# lab_1_kapustin_usb_spi.net
KiCad netlist of a schematic drawn in Altium Designer
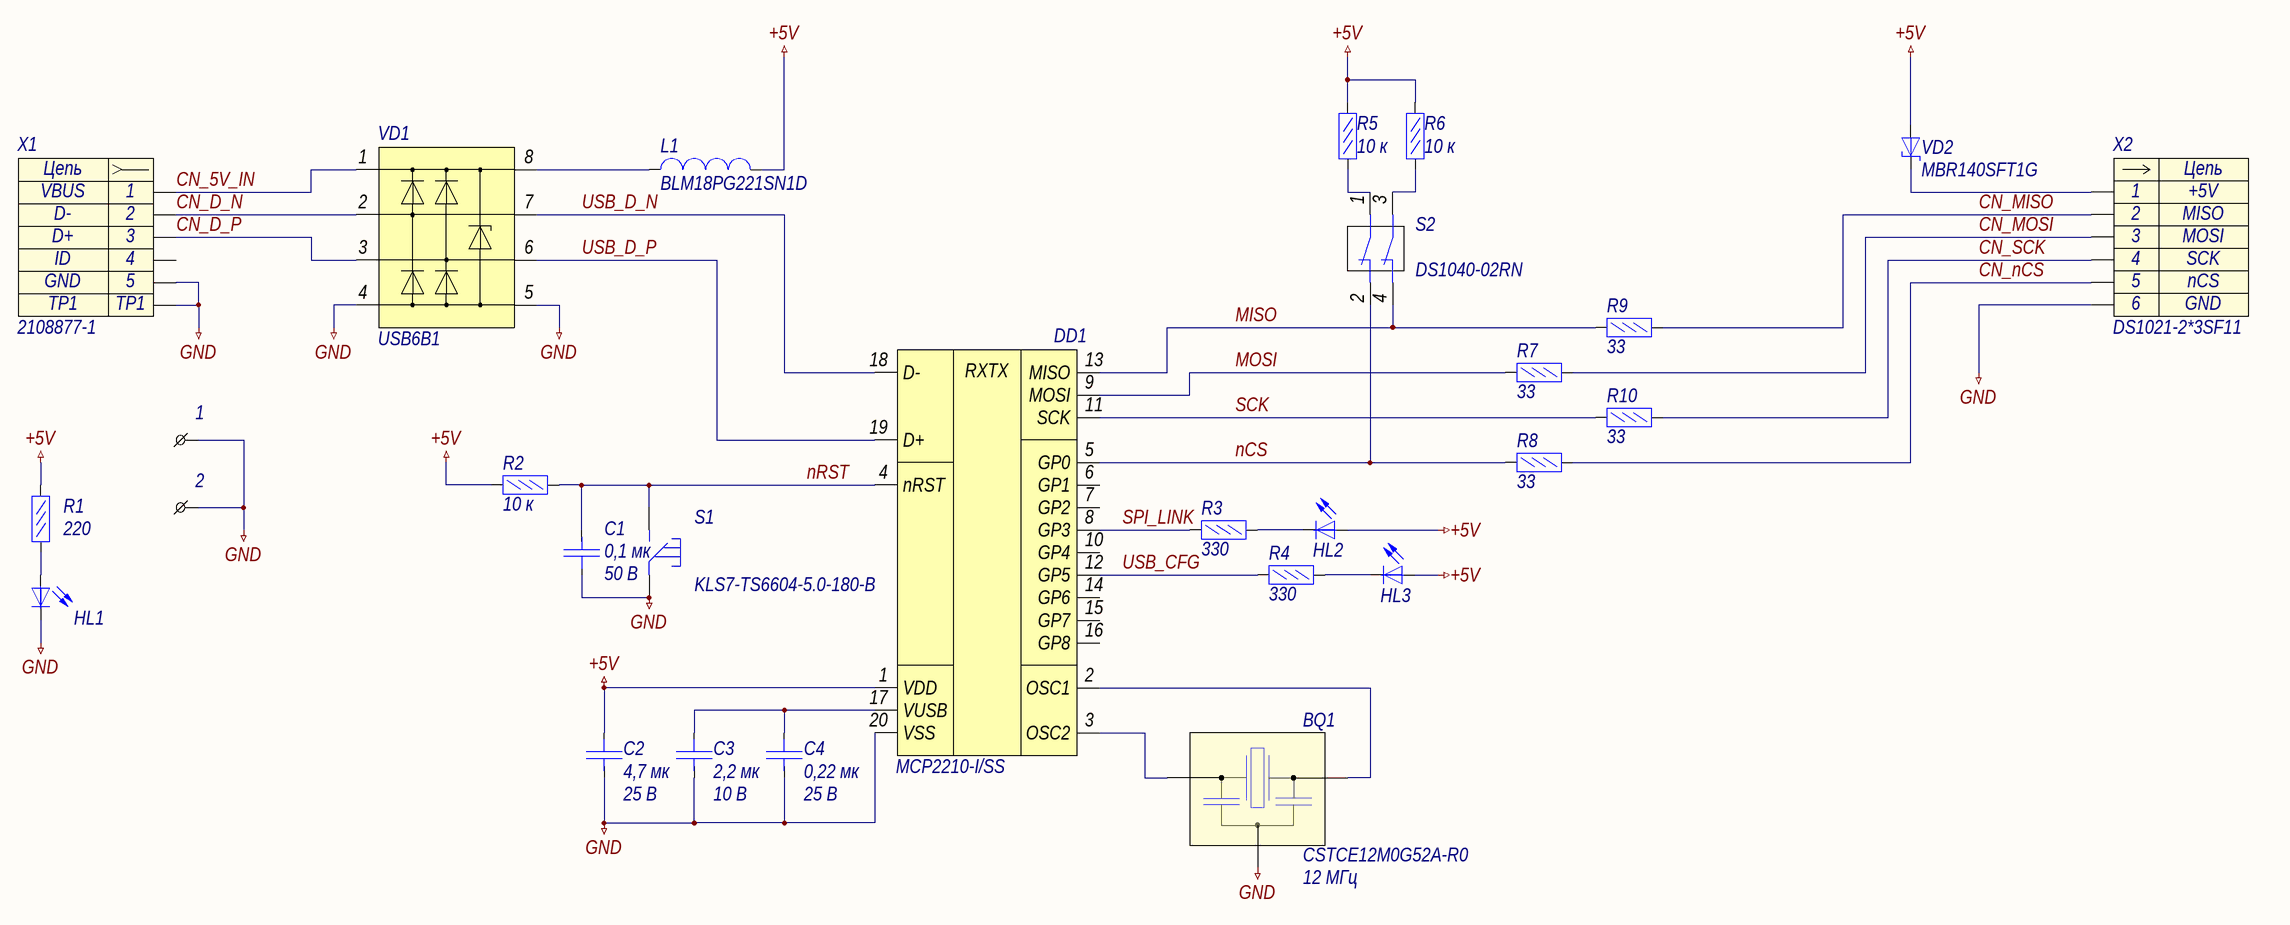
[diagram p0: lab_1_kapustin_usb_spi.SchDoc]

(export (version "E")
  (design (tool "Eeschema 10.0.6"))
  (components
    (comp (ref "1")
      (value "MOUNTING_HOLE")
      (footprint "HOLE_1,6X3,3")
      (libsource (lib "kravt_lib") (part "MOUNTING_HOLE"))
    )
    (comp (ref "2")
      (value "MOUNTING_HOLE")
      (footprint "HOLE_1,6X3,3")
      (libsource (lib "kravt_lib") (part "MOUNTING_HOLE"))
    )
    (comp (ref "BQ1")
      (value "CSTCE12M0G52A-R0")
      (footprint "CSTCE-3_320x130x40")
      (fields (field (name "ЧАСТОТА") "12 МГц"))
      (libsource (lib "kravt_lib") (part "cstce12m0g52a-r0"))
    )
    (comp (ref "C1")
      (value "0,1 мк")
      (footprint "C0603")
      (description "Конденсатор")
      (fields (field (name "НАПРЯЖЕНИЕ") "50 В"))
      (libsource (lib "kravt_lib") (part "c"))
    )
    (comp (ref "C2")
      (value "4,7 мк")
      (footprint "C0603")
      (description "Конденсатор")
      (fields (field (name "НАПРЯЖЕНИЕ") "25 В"))
      (libsource (lib "kravt_lib") (part "c"))
    )
    (comp (ref "C3")
      (value "2,2 мк")
      (footprint "C0603")
      (description "Конденсатор")
      (fields (field (name "НАПРЯЖЕНИЕ") "10 В"))
      (libsource (lib "kravt_lib") (part "c"))
    )
    (comp (ref "C4")
      (value "0,22 мк")
      (footprint "C0603")
      (description "Конденсатор")
      (fields (field (name "НАПРЯЖЕНИЕ") "25 В"))
      (libsource (lib "kravt_lib") (part "c"))
    )
    (comp (ref "DD1")
      (value "MCP2210-I/SS")
      (footprint "ssop-20_780x720x200:SSOP-20_780x720x200")
      (libsource (lib "MCP2210-ISS") (part "MCP2210ISS"))
    )
    (comp (ref "HL1")
      (value "KP-1608SGC")
      (footprint "D0603")
      (libsource (lib "kravt_lib") (part "DIODE_LED"))
    )
    (comp (ref "HL2")
      (value "KP-1608YC")
      (footprint "D0603")
      (libsource (lib "kravt_lib") (part "DIODE_LED"))
    )
    (comp (ref "HL3")
      (value "KP-1608YC")
      (footprint "D0603")
      (libsource (lib "kravt_lib") (part "DIODE_LED"))
    )
    (comp (ref "L1")
      (value "BLM18PG221SN1D")
      (footprint "L0603")
      (libsource (lib "kravt_lib") (part "L_BEAD"))
    )
    (comp (ref "R1")
      (value "220")
      (footprint "R0603")
      (description "Резистор 0,063Вт")
      (libsource (lib "kravt_lib") (part "R-0.063W"))
    )
    (comp (ref "R2")
      (value "10 к")
      (footprint "R0603")
      (description "Резистор 0,063Вт")
      (libsource (lib "") (part "R-0.063W_1"))
    )
    (comp (ref "R3")
      (value "330")
      (footprint "R0603")
      (description "Резистор 0,063Вт")
      (libsource (lib "") (part "R-0.063W_1"))
    )
    (comp (ref "R4")
      (value "330")
      (footprint "R0603")
      (description "Резистор 0,063Вт")
      (libsource (lib "") (part "R-0.063W_1"))
    )
    (comp (ref "R5")
      (value "10 к")
      (footprint "R0603")
      (description "Резистор 0,063Вт")
      (libsource (lib "kravt_lib") (part "R-0.063W"))
    )
    (comp (ref "R6")
      (value "10 к")
      (footprint "R0603")
      (description "Резистор 0,063Вт")
      (libsource (lib "kravt_lib") (part "R-0.063W"))
    )
    (comp (ref "R7")
      (value "33")
      (footprint "R0603")
      (description "Резистор 0,063Вт")
      (libsource (lib "") (part "R-0.063W_1"))
    )
    (comp (ref "R8")
      (value "33")
      (footprint "R0603")
      (description "Резистор 0,063Вт")
      (libsource (lib "") (part "R-0.063W_1"))
    )
    (comp (ref "R9")
      (value "33")
      (footprint "R0603")
      (description "Резистор 0,063Вт")
      (libsource (lib "") (part "R-0.063W_1"))
    )
    (comp (ref "R10")
      (value "33")
      (footprint "R0603")
      (description "Резистор 0,063Вт")
      (libsource (lib "") (part "R-0.063W_1"))
    )
    (comp (ref "S1")
      (value "KLS7-TS6604-5.0-180-B")
      (footprint "KLS7-TS6604_500")
      (libsource (lib "kravt_lib") (part "BUTTON"))
    )
    (comp (ref "S2")
      (value "DS1040-02RN")
      (footprint "DS1040-02RN")
      (libsource (lib "kravt_lib") (part "SWITCH_2C"))
    )
    (comp (ref "VD1") (value "USB6B1") (footprint "SO-8") (libsource (lib "kravt_lib") (part "USB6B1")))
    (comp (ref "VD2")
      (value "MBR140SFT1G")
      (footprint "SOD-123FL_290X180X98")
      (libsource (lib "kravt_lib") (part "DIODE_SHOTTKY"))
    )
    (comp (ref "X1")
      (value "2108877-1")
      (footprint "2108877-1")
      (libsource (lib "2108877-1_micro_usb-b") (part "2108877-1_micro_usb-b"))
    )
    (comp (ref "X2")
      (value "DS1021-2*3SF11")
      (footprint "PLS-2,54-2X3-THT-V")
      (libsource (lib "kravt_lib") (part "HEADER-6_PLG"))
    )
  )
  (nets
    (net (code "1") (name "+5V") (class "Default")
      (node (ref "C2") (pin "1") (pinfunction "1_1") (pintype "passive"))
      (node (ref "DD1") (pin "1") (pinfunction "VDD_1") (pintype "passive"))
      (node (ref "HL2") (pin "1") (pinfunction "A_1") (pintype "passive"))
      (node (ref "HL3") (pin "1") (pinfunction "A_1") (pintype "passive"))
      (node (ref "L1") (pin "2") (pinfunction "2_2") (pintype "passive"))
      (node (ref "R1") (pin "2") (pinfunction "2_2") (pintype "passive"))
      (node (ref "R2") (pin "1") (pinfunction "1_1") (pintype "passive"))
      (node (ref "R5") (pin "2") (pinfunction "2_2") (pintype "passive"))
      (node (ref "R6") (pin "2") (pinfunction "2_2") (pintype "passive"))
      (node (ref "VD2") (pin "1") (pinfunction "A_1") (pintype "passive"))
    )
    (net (code "2") (name "/CN_5V_IN") (class "Default")
      (node (ref "VD1") (pin "1") (pintype "passive"))
      (node (ref "X1") (pin "1") (pinfunction "1_1") (pintype "passive"))
    )
    (net (code "3") (name "/CN_D_N") (class "Default")
      (node (ref "VD1") (pin "2") (pintype "passive"))
      (node (ref "X1") (pin "2") (pinfunction "2_2") (pintype "passive"))
    )
    (net (code "4") (name "/CN_D_P") (class "Default")
      (node (ref "VD1") (pin "3") (pintype "passive"))
      (node (ref "X1") (pin "3") (pinfunction "3_3") (pintype "passive"))
    )
    (net (code "5") (name "/CN_MISO") (class "Default")
      (node (ref "R9") (pin "2") (pinfunction "2_2") (pintype "passive"))
      (node (ref "X2") (pin "2") (pinfunction "2_2") (pintype "passive"))
    )
    (net (code "6") (name "/CN_MOSI") (class "Default")
      (node (ref "R7") (pin "2") (pinfunction "2_2") (pintype "passive"))
      (node (ref "X2") (pin "3") (pinfunction "3_3") (pintype "passive"))
    )
    (net (code "7") (name "/CN_SCK") (class "Default")
      (node (ref "R10") (pin "2") (pinfunction "2_2") (pintype "passive"))
      (node (ref "X2") (pin "4") (pinfunction "4_4") (pintype "passive"))
    )
    (net (code "8") (name "/CN_nCS") (class "Default")
      (node (ref "R8") (pin "2") (pinfunction "2_2") (pintype "passive"))
      (node (ref "X2") (pin "5") (pinfunction "5_5") (pintype "passive"))
    )
    (net (code "9") (name "/MISO") (class "Default")
      (node (ref "DD1") (pin "13") (pinfunction "MISO_13") (pintype "passive"))
      (node (ref "R9") (pin "1") (pinfunction "1_1") (pintype "passive"))
      (node (ref "S2") (pin "4") (pinfunction "4_4") (pintype "passive"))
    )
    (net (code "10") (name "/MOSI") (class "Default")
      (node (ref "DD1") (pin "9") (pinfunction "MOSI_9") (pintype "passive"))
      (node (ref "R7") (pin "1") (pinfunction "1_1") (pintype "passive"))
    )
    (net (code "11") (name "/SCK") (class "Default")
      (node (ref "DD1") (pin "11") (pinfunction "SCK_11") (pintype "passive"))
      (node (ref "R10") (pin "1") (pinfunction "1_1") (pintype "passive"))
    )
    (net (code "12") (name "/SPI_LINK") (class "Default")
      (node (ref "DD1") (pin "8") (pinfunction "GP3_8") (pintype "passive"))
      (node (ref "R3") (pin "1") (pinfunction "1_1") (pintype "passive"))
    )
    (net (code "13") (name "/USB_CFG") (class "Default")
      (node (ref "DD1") (pin "12") (pinfunction "GP5_12") (pintype "passive"))
      (node (ref "R4") (pin "1") (pinfunction "1_1") (pintype "passive"))
    )
    (net (code "14") (name "/USB_D_N") (class "Default")
      (node (ref "DD1") (pin "18") (pinfunction "D-_18") (pintype "passive"))
      (node (ref "VD1") (pin "7") (pintype "passive"))
    )
    (net (code "15") (name "/USB_D_P") (class "Default")
      (node (ref "DD1") (pin "19") (pinfunction "D+_19") (pintype "passive"))
      (node (ref "VD1") (pin "6") (pintype "passive"))
    )
    (net (code "16") (name "/nCS") (class "Default")
      (node (ref "DD1") (pin "5") (pinfunction "GP0_5") (pintype "passive"))
      (node (ref "R8") (pin "1") (pinfunction "1_1") (pintype "passive"))
      (node (ref "S2") (pin "2") (pinfunction "2_2") (pintype "passive"))
    )
    (net (code "17") (name "/nRST") (class "Default")
      (node (ref "C1") (pin "2") (pinfunction "2_2") (pintype "passive"))
      (node (ref "DD1") (pin "4") (pinfunction "nRST_4") (pintype "passive"))
      (node (ref "R2") (pin "2") (pinfunction "2_2") (pintype "passive"))
      (node (ref "S1") (pin "2") (pinfunction "2_2") (pintype "passive"))
    )
    (net (code "18") (name "GND") (class "Default")
      (node (ref "1") (pin "1") (pinfunction "1_1") (pintype "passive"))
      (node (ref "2") (pin "1") (pinfunction "1_1") (pintype "passive"))
      (node (ref "BQ1") (pin "2") (pinfunction "2_2") (pintype "passive"))
      (node (ref "C1") (pin "1") (pinfunction "1_1") (pintype "passive"))
      (node (ref "C2") (pin "2") (pinfunction "2_2") (pintype "passive"))
      (node (ref "C3") (pin "2") (pinfunction "2_2") (pintype "passive"))
      (node (ref "C4") (pin "2") (pinfunction "2_2") (pintype "passive"))
      (node (ref "DD1") (pin "20") (pinfunction "VSS_20") (pintype "passive"))
      (node (ref "HL1") (pin "2") (pinfunction "K_2") (pintype "passive"))
      (node (ref "S1") (pin "1") (pinfunction "1_1") (pintype "passive"))
      (node (ref "VD1") (pin "4") (pintype "passive"))
      (node (ref "VD1") (pin "5") (pintype "passive"))
      (node (ref "X1") (pin "5") (pinfunction "5_5") (pintype "passive"))
      (node (ref "X1") (pin "TP1") (pinfunction "TP1_TP1") (pintype "passive"))
      (node (ref "X2") (pin "6") (pinfunction "6_6") (pintype "passive"))
    )
    (net (code "19") (name "Net-(DD1-OSC1)") (class "Default")
      (node (ref "BQ1") (pin "1") (pinfunction "1_1") (pintype "passive"))
      (node (ref "DD1") (pin "2") (pinfunction "OSC1_2") (pintype "passive"))
    )
    (net (code "20") (name "Net-(DD1-OSC2)") (class "Default")
      (node (ref "BQ1") (pin "3") (pinfunction "3_3") (pintype "passive"))
      (node (ref "DD1") (pin "3") (pinfunction "OSC2_3") (pintype "passive"))
    )
    (net (code "21") (name "Net-(DD1-VUSB)") (class "Default")
      (node (ref "C3") (pin "1") (pinfunction "1_1") (pintype "passive"))
      (node (ref "C4") (pin "1") (pinfunction "1_1") (pintype "passive"))
      (node (ref "DD1") (pin "17") (pinfunction "VUSB_17") (pintype "passive"))
    )
    (net (code "22") (name "Net-(HL1-A)") (class "Default")
      (node (ref "HL1") (pin "1") (pinfunction "A_1") (pintype "passive"))
      (node (ref "R1") (pin "1") (pinfunction "1_1") (pintype "passive"))
    )
    (net (code "23") (name "Net-(HL2-K)") (class "Default")
      (node (ref "HL2") (pin "2") (pinfunction "K_2") (pintype "passive"))
      (node (ref "R3") (pin "2") (pinfunction "2_2") (pintype "passive"))
    )
    (net (code "24") (name "Net-(HL3-K)") (class "Default")
      (node (ref "HL3") (pin "2") (pinfunction "K_2") (pintype "passive"))
      (node (ref "R4") (pin "2") (pinfunction "2_2") (pintype "passive"))
    )
    (net (code "25") (name "Net-(L1-Pad1)") (class "Default")
      (node (ref "L1") (pin "1") (pinfunction "1_1") (pintype "passive"))
      (node (ref "VD1") (pin "8") (pintype "passive"))
    )
    (net (code "26") (name "Net-(R5-Pad1)") (class "Default")
      (node (ref "R5") (pin "1") (pinfunction "1_1") (pintype "passive"))
      (node (ref "S2") (pin "1") (pinfunction "1_1") (pintype "passive"))
    )
    (net (code "27") (name "Net-(R6-Pad1)") (class "Default")
      (node (ref "R6") (pin "1") (pinfunction "1_1") (pintype "passive"))
      (node (ref "S2") (pin "3") (pinfunction "3_3") (pintype "passive"))
    )
    (net (code "28") (name "Net-(VD2-K)") (class "Default")
      (node (ref "VD2") (pin "2") (pinfunction "K_2") (pintype "passive"))
      (node (ref "X2") (pin "1") (pinfunction "1_1") (pintype "passive"))
    )
    (net (code "29") (name "unconnected-(DD1-GP1-Pad6)") (class "Default")
      (node (ref "DD1") (pin "6") (pinfunction "GP1_6") (pintype "passive"))
    )
    (net (code "30") (name "unconnected-(DD1-GP2-Pad7)") (class "Default")
      (node (ref "DD1") (pin "7") (pinfunction "GP2_7") (pintype "passive"))
    )
    (net (code "31") (name "unconnected-(DD1-GP4-Pad10)") (class "Default")
      (node (ref "DD1") (pin "10") (pinfunction "GP4_10") (pintype "passive"))
    )
    (net (code "32") (name "unconnected-(DD1-GP6-Pad14)") (class "Default")
      (node (ref "DD1") (pin "14") (pinfunction "GP6_14") (pintype "passive"))
    )
    (net (code "33") (name "unconnected-(DD1-GP7-Pad15)") (class "Default")
      (node (ref "DD1") (pin "15") (pinfunction "GP7_15") (pintype "passive"))
    )
    (net (code "34") (name "unconnected-(DD1-GP8-Pad16)") (class "Default")
      (node (ref "DD1") (pin "16") (pinfunction "GP8_16") (pintype "passive"))
    )
    (net (code "35") (name "unconnected-(X1-Pad4)") (class "Default")
      (node (ref "X1") (pin "4") (pinfunction "4_4") (pintype "passive"))
    )
  )
)
